# mimamori-hat-v03.net
KiCad netlist of a schematic drawn in EAGLE
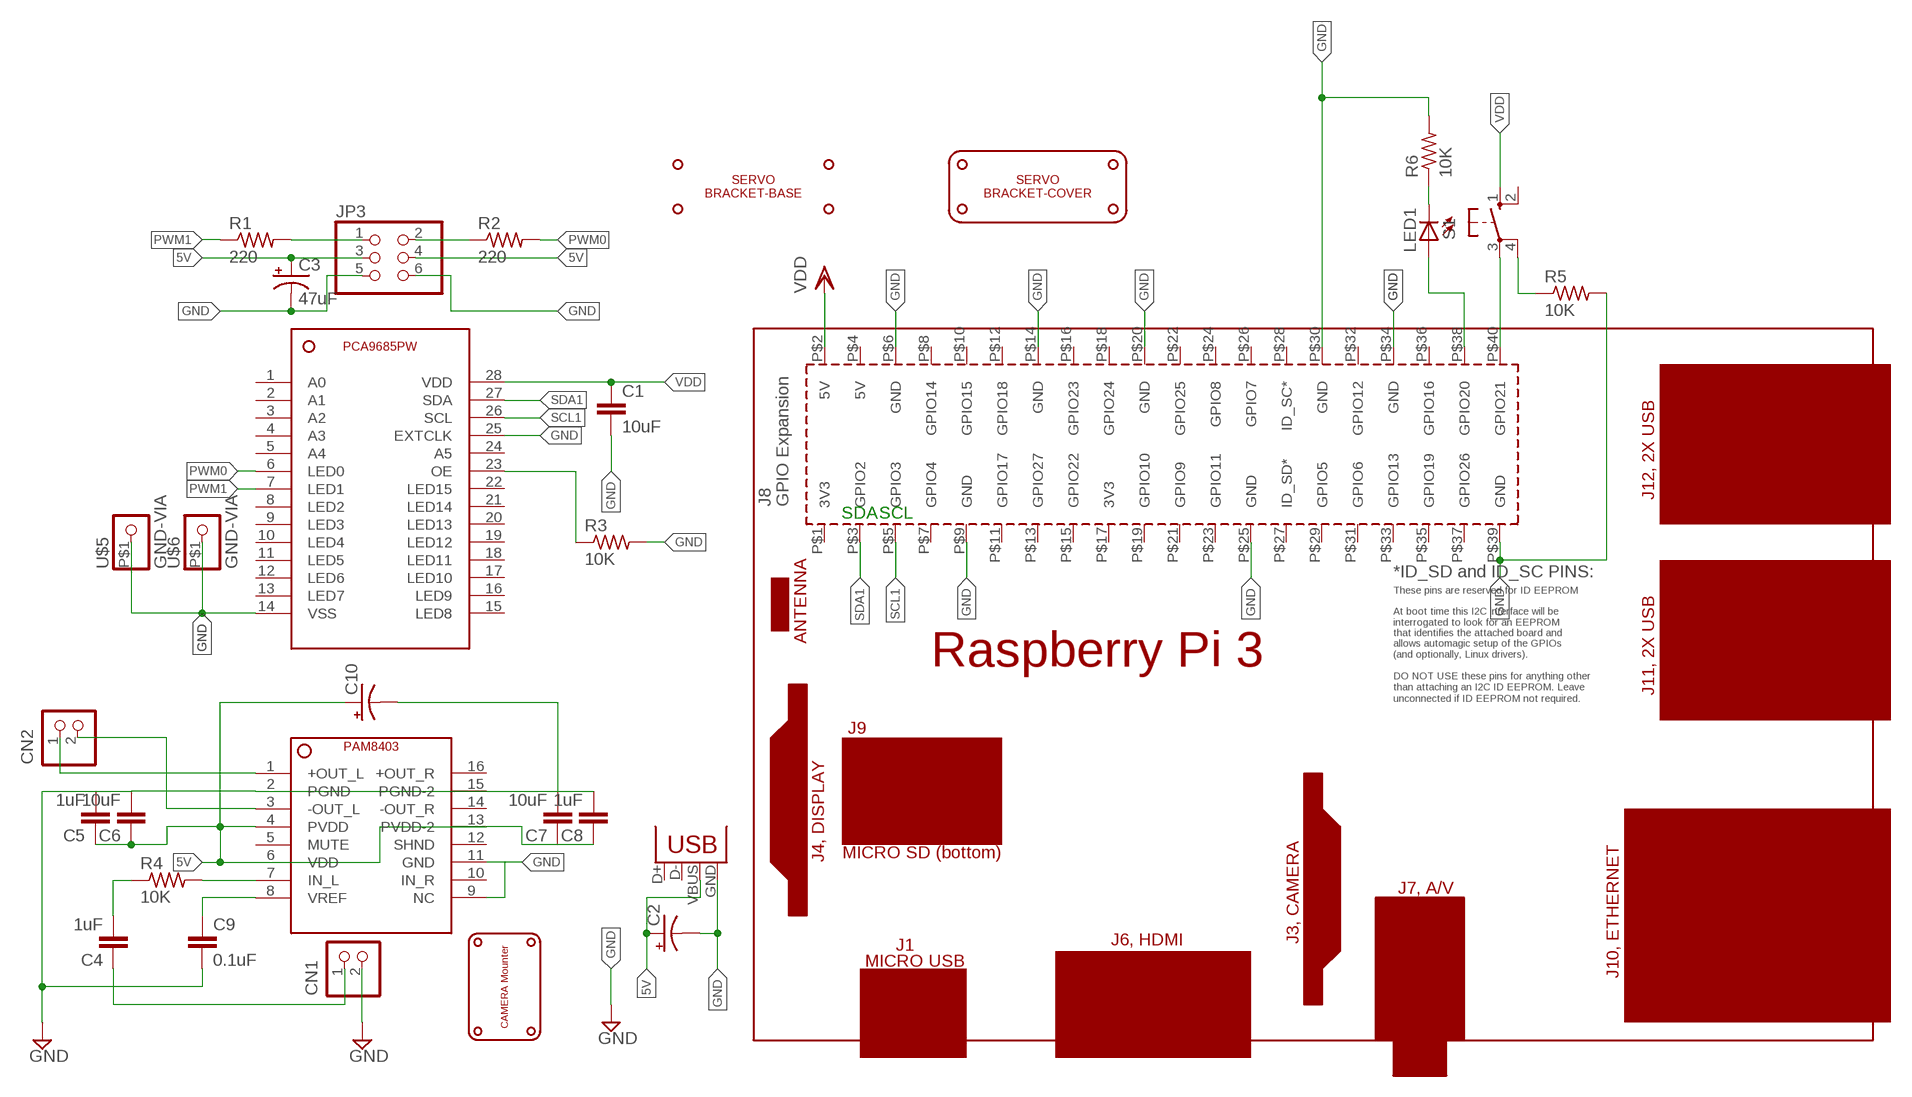
[diagram p0: schematic, sheet 1]

(export (version "E")
  (design (tool "Eeschema 10.0.6"))
  (components
    (comp (ref "C1")
      (value "10uF")
      (footprint "eagle-import:C0805")
      (libsource (lib "eagle-import") (part "C-EUC0805"))
    )
    (comp (ref "C2")
      (value "CPOL-US153CLV-0810")
      (footprint "eagle-import:153CLV-0810")
      (libsource (lib "eagle-import") (part "CPOL-US153CLV-0810"))
    )
    (comp (ref "C3")
      (value "47uF")
      (footprint "eagle-import:153CLV-0605")
      (libsource (lib "eagle-import") (part "CPOL-US153CLV-0605"))
    )
    (comp (ref "C4")
      (value "1uF")
      (footprint "eagle-import:C0805")
      (libsource (lib "eagle-import") (part "C-EUC0805"))
    )
    (comp (ref "C5")
      (value "1uF")
      (footprint "eagle-import:C0805")
      (libsource (lib "eagle-import") (part "C-EUC0805"))
    )
    (comp (ref "C6")
      (value "10uF")
      (footprint "eagle-import:C0805")
      (libsource (lib "eagle-import") (part "C-EUC0805"))
    )
    (comp (ref "C7")
      (value "10uF")
      (footprint "eagle-import:C0805")
      (libsource (lib "eagle-import") (part "C-EUC0805"))
    )
    (comp (ref "C8")
      (value "1uF")
      (footprint "eagle-import:C0805")
      (libsource (lib "eagle-import") (part "C-EUC0805"))
    )
    (comp (ref "C9")
      (value "0.1uF")
      (footprint "eagle-import:C0805")
      (libsource (lib "eagle-import") (part "C-EUC0805"))
    )
    (comp (ref "C10")
      (value "CPOL-US153CLV-0810")
      (footprint "eagle-import:153CLV-0810")
      (libsource (lib "eagle-import") (part "CPOL-US153CLV-0810"))
    )
    (comp (ref "CN1")
      (value "B2B-PH-K-S")
      (footprint "eagle-import:B2B-PH-K-S")
      (libsource (lib "eagle-import") (part "B2B-PH-K-S"))
    )
    (comp (ref "CN2")
      (value "B2B-PH-K-S")
      (footprint "eagle-import:B2B-PH-K-S")
      (libsource (lib "eagle-import") (part "B2B-PH-K-S"))
    )
    (comp (ref "JP1")
      (value "USB-MICROB")
      (footprint "eagle-import:USB-MICROB")
      (libsource (lib "eagle-import") (part "USB-MICROB"))
    )
    (comp (ref "JP3")
      (value "PINHD-2X3")
      (footprint "eagle-import:2X03")
      (libsource (lib "eagle-import") (part "PINHD-2X3"))
    )
    (comp (ref "LED1")
      (value "LED3MM")
      (footprint "eagle-import:LED3MM")
      (libsource (lib "eagle-import") (part "LED3MM"))
    )
    (comp (ref "PCB1")
      (value "RPI3")
      (footprint "eagle-import:RPI3")
      (libsource (lib "eagle-import") (part "RPI3"))
    )
    (comp (ref "R1")
      (value "220")
      (footprint "eagle-import:R0805")
      (libsource (lib "eagle-import") (part "R-US_R0805"))
    )
    (comp (ref "R2")
      (value "220")
      (footprint "eagle-import:R0805")
      (libsource (lib "eagle-import") (part "R-US_R0805"))
    )
    (comp (ref "R3")
      (value "10K")
      (footprint "eagle-import:R0805")
      (libsource (lib "eagle-import") (part "R-US_R0805"))
    )
    (comp (ref "R4")
      (value "10K")
      (footprint "eagle-import:R0805")
      (libsource (lib "eagle-import") (part "R-US_R0805"))
    )
    (comp (ref "R5")
      (value "10K")
      (footprint "eagle-import:R0805")
      (libsource (lib "eagle-import") (part "R-US_R0805"))
    )
    (comp (ref "R6")
      (value "10K")
      (footprint "eagle-import:R0805")
      (libsource (lib "eagle-import") (part "R-US_R0805"))
    )
    (comp (ref "S1")
      (value "10-XX")
      (footprint "eagle-import:B3F-10XX")
      (fields (field (name "MPN") "B3F-1000"))
      (libsource (lib "eagle-import") (part "10-XX"))
    )
    (comp (ref "U$1")
      (value "PAM8403")
      (footprint "eagle-import:SOP16")
      (libsource (lib "eagle-import") (part "PAM8403"))
    )
    (comp (ref "U$2")
      (value "PCA9685PW")
      (footprint "eagle-import:TSSOP28")
      (libsource (lib "eagle-import") (part "PCA9685PW"))
    )
    (comp (ref "U$3")
      (value "CAMERA-MOUNTER")
      (footprint "eagle-import:CAMERA-MOUNTER")
      (libsource (lib "eagle-import") (part "CAMERA-MOUNTER"))
    )
    (comp (ref "U$4")
      (value "SERVO-BRACKET-BASE")
      (footprint "eagle-import:SERVO-BRACKET")
      (libsource (lib "eagle-import") (part "SERVO-BRACKET-BASE"))
    )
    (comp (ref "U$5")
      (value "GND-VIA")
      (footprint "eagle-import:GND-VIA")
      (libsource (lib "eagle-import") (part "GND-VIA"))
    )
    (comp (ref "U$6")
      (value "GND-VIA")
      (footprint "eagle-import:GND-VIA")
      (libsource (lib "eagle-import") (part "GND-VIA"))
    )
    (comp (ref "U$7")
      (value "SERVO-BRACKER-COVER")
      (footprint "eagle-import:SERVO-BRACKET-COVER")
      (libsource (lib "eagle-import") (part "SERVO-BRACKER-COVER"))
    )
  )
  (nets
    (net (code "1") (name "5V") (class "Default")
      (node (ref "C10") (pin "+") (pinfunction "+_+") (pintype "passive"))
      (node (ref "C2") (pin "+") (pinfunction "+_+") (pintype "passive"))
      (node (ref "C3") (pin "+") (pinfunction "+_+") (pintype "passive"))
      (node (ref "C5") (pin "1") (pinfunction "1_1") (pintype "passive"))
      (node (ref "C6") (pin "1") (pinfunction "1_1") (pintype "passive"))
      (node (ref "C7") (pin "1") (pinfunction "1_1") (pintype "passive"))
      (node (ref "C8") (pin "1") (pinfunction "1_1") (pintype "passive"))
      (node (ref "JP1") (pin "VBUS") (pinfunction "VBUS_VBUS") (pintype "bidirectional"))
      (node (ref "JP3") (pin "3") (pinfunction "3_3") (pintype "passive"))
      (node (ref "JP3") (pin "4") (pinfunction "4_4") (pintype "passive"))
      (node (ref "U$1") (pin "13") (pinfunction "PVDD-2_13") (pintype "bidirectional"))
      (node (ref "U$1") (pin "4") (pinfunction "PVDD_4") (pintype "bidirectional"))
      (node (ref "U$1") (pin "6") (pinfunction "VDD_6") (pintype "bidirectional"))
    )
    (net (code "2") (name "GND") (class "Default")
      (node (ref "C1") (pin "2") (pinfunction "2_2") (pintype "passive"))
      (node (ref "C10") (pin "-") (pinfunction "-_-") (pintype "passive"))
      (node (ref "C2") (pin "-") (pinfunction "-_-") (pintype "passive"))
      (node (ref "C3") (pin "-") (pinfunction "-_-") (pintype "passive"))
      (node (ref "C5") (pin "2") (pinfunction "2_2") (pintype "passive"))
      (node (ref "C6") (pin "2") (pinfunction "2_2") (pintype "passive"))
      (node (ref "C7") (pin "2") (pinfunction "2_2") (pintype "passive"))
      (node (ref "C8") (pin "2") (pinfunction "2_2") (pintype "passive"))
      (node (ref "C9") (pin "2") (pinfunction "2_2") (pintype "passive"))
      (node (ref "CN1") (pin "2") (pinfunction "2_2") (pintype "passive"))
      (node (ref "JP1") (pin "GND") (pinfunction "GND_GND") (pintype "bidirectional"))
      (node (ref "JP3") (pin "5") (pinfunction "5_5") (pintype "passive"))
      (node (ref "JP3") (pin "6") (pinfunction "6_6") (pintype "passive"))
      (node (ref "PCB1") (pin "P$14") (pinfunction "GND_P$14") (pintype "bidirectional"))
      (node (ref "PCB1") (pin "P$20") (pinfunction "GND_P$20") (pintype "bidirectional"))
      (node (ref "PCB1") (pin "P$25") (pinfunction "GND_P$25") (pintype "bidirectional"))
      (node (ref "PCB1") (pin "P$30") (pinfunction "GND_P$30") (pintype "bidirectional"))
      (node (ref "PCB1") (pin "P$34") (pinfunction "GND_P$34") (pintype "bidirectional"))
      (node (ref "PCB1") (pin "P$39") (pinfunction "GND_P$39") (pintype "bidirectional"))
      (node (ref "PCB1") (pin "P$6") (pinfunction "GND_P$6") (pintype "bidirectional"))
      (node (ref "PCB1") (pin "P$9") (pinfunction "GND_P$9") (pintype "bidirectional"))
      (node (ref "R3") (pin "2") (pinfunction "2_2") (pintype "passive"))
      (node (ref "R5") (pin "2") (pinfunction "2_2") (pintype "passive"))
      (node (ref "R6") (pin "2") (pinfunction "2_2") (pintype "passive"))
      (node (ref "U$1") (pin "11") (pinfunction "GND_11") (pintype "bidirectional"))
      (node (ref "U$1") (pin "15") (pinfunction "PGND-2_15") (pintype "bidirectional"))
      (node (ref "U$1") (pin "2") (pinfunction "PGND_2") (pintype "bidirectional"))
      (node (ref "U$1") (pin "9") (pinfunction "NC_9") (pintype "bidirectional"))
      (node (ref "U$2") (pin "14") (pinfunction "VSS_14") (pintype "bidirectional"))
      (node (ref "U$2") (pin "25") (pinfunction "EXTCLK_25") (pintype "bidirectional"))
      (node (ref "U$5") (pin "P$1") (pinfunction "1_P$1") (pintype "passive"))
      (node (ref "U$6") (pin "P$1") (pinfunction "1_P$1") (pintype "passive"))
    )
    (net (code "3") (name "Net-(C4-Pad1)") (class "Default")
      (node (ref "C4") (pin "1") (pinfunction "1_1") (pintype "passive"))
      (node (ref "CN1") (pin "1") (pinfunction "1_1") (pintype "passive"))
    )
    (net (code "4") (name "Net-(C4-Pad2)") (class "Default")
      (node (ref "C4") (pin "2") (pinfunction "2_2") (pintype "passive"))
      (node (ref "R4") (pin "1") (pinfunction "1_1") (pintype "passive"))
    )
    (net (code "5") (name "Net-(JP3-Pad1)") (class "Default")
      (node (ref "JP3") (pin "1") (pinfunction "1_1") (pintype "passive"))
      (node (ref "R1") (pin "2") (pinfunction "2_2") (pintype "passive"))
    )
    (net (code "6") (name "Net-(JP3-Pad2)") (class "Default")
      (node (ref "JP3") (pin "2") (pinfunction "2_2") (pintype "passive"))
      (node (ref "R2") (pin "1") (pinfunction "1_1") (pintype "passive"))
    )
    (net (code "7") (name "Net-(LED1-C)") (class "Default")
      (node (ref "LED1") (pin "K") (pinfunction "C_K") (pintype "passive"))
      (node (ref "R6") (pin "1") (pinfunction "1_1") (pintype "passive"))
    )
    (net (code "8") (name "Net-(PCB1-GPIO20)") (class "Default")
      (node (ref "LED1") (pin "A") (pinfunction "A_A") (pintype "passive"))
      (node (ref "PCB1") (pin "P$38") (pinfunction "GPIO20_P$38") (pintype "bidirectional"))
    )
    (net (code "9") (name "Net-(PCB1-GPIO21)") (class "Default")
      (node (ref "PCB1") (pin "P$40") (pinfunction "GPIO21_P$40") (pintype "bidirectional"))
      (node (ref "S1") (pin "3") (pinfunction "P_3") (pintype "passive"))
    )
    (net (code "10") (name "Net-(S1-P1)") (class "Default")
      (node (ref "R5") (pin "1") (pinfunction "1_1") (pintype "passive"))
      (node (ref "S1") (pin "4") (pinfunction "P1_4") (pintype "passive"))
    )
    (net (code "11") (name "Net-(U$1-+OUT_L)") (class "Default")
      (node (ref "CN2") (pin "1") (pinfunction "1_1") (pintype "passive"))
      (node (ref "U$1") (pin "1") (pinfunction "+OUT_L_1") (pintype "bidirectional"))
    )
    (net (code "12") (name "Net-(U$1--OUT_L)") (class "Default")
      (node (ref "CN2") (pin "2") (pinfunction "2_2") (pintype "passive"))
      (node (ref "U$1") (pin "3") (pinfunction "-OUT_L_3") (pintype "bidirectional"))
    )
    (net (code "13") (name "Net-(U$1-IN_L)") (class "Default")
      (node (ref "R4") (pin "2") (pinfunction "2_2") (pintype "passive"))
      (node (ref "U$1") (pin "7") (pinfunction "IN_L_7") (pintype "bidirectional"))
    )
    (net (code "14") (name "Net-(U$1-VREF)") (class "Default")
      (node (ref "C9") (pin "1") (pinfunction "1_1") (pintype "passive"))
      (node (ref "U$1") (pin "8") (pinfunction "VREF_8") (pintype "bidirectional"))
    )
    (net (code "15") (name "Net-(U$2-OE)") (class "Default")
      (node (ref "R3") (pin "1") (pinfunction "1_1") (pintype "passive"))
      (node (ref "U$2") (pin "23") (pinfunction "OE_23") (pintype "bidirectional"))
    )
    (net (code "16") (name "PWM0") (class "Default")
      (node (ref "R2") (pin "2") (pinfunction "2_2") (pintype "passive"))
      (node (ref "U$2") (pin "6") (pinfunction "LED0_6") (pintype "bidirectional"))
    )
    (net (code "17") (name "PWM1") (class "Default")
      (node (ref "R1") (pin "1") (pinfunction "1_1") (pintype "passive"))
      (node (ref "U$2") (pin "7") (pinfunction "LED1_7") (pintype "bidirectional"))
    )
    (net (code "18") (name "SCL1") (class "Default")
      (node (ref "PCB1") (pin "P$5") (pinfunction "GPIO3_P$5") (pintype "bidirectional"))
      (node (ref "U$2") (pin "26") (pinfunction "SCL_26") (pintype "bidirectional"))
    )
    (net (code "19") (name "SDA1") (class "Default")
      (node (ref "PCB1") (pin "P$3") (pinfunction "GPIO2_P$3") (pintype "bidirectional"))
      (node (ref "U$2") (pin "27") (pinfunction "SDA_27") (pintype "bidirectional"))
    )
    (net (code "20") (name "VDD") (class "Default")
      (node (ref "C1") (pin "1") (pinfunction "1_1") (pintype "passive"))
      (node (ref "PCB1") (pin "P$2") (pinfunction "5V_P$2") (pintype "bidirectional"))
      (node (ref "S1") (pin "1") (pinfunction "S_1") (pintype "passive"))
      (node (ref "U$2") (pin "28") (pinfunction "VDD_28") (pintype "bidirectional"))
    )
    (net (code "21") (name "unconnected-(JP1-PadD+)") (class "Default")
      (node (ref "JP1") (pin "D+") (pinfunction "D+_D+") (pintype "bidirectional"))
    )
    (net (code "22") (name "unconnected-(JP1-PadD-)") (class "Default")
      (node (ref "JP1") (pin "D-") (pinfunction "D-_D-") (pintype "bidirectional"))
    )
    (net (code "23") (name "unconnected-(PCB1-3V3-PadP$1)") (class "Default")
      (node (ref "PCB1") (pin "P$1") (pinfunction "3V3_P$1") (pintype "bidirectional"))
    )
    (net (code "24") (name "unconnected-(PCB1-3V3-PadP$17)") (class "Default")
      (node (ref "PCB1") (pin "P$17") (pinfunction "3V3_P$17") (pintype "bidirectional"))
    )
    (net (code "25") (name "unconnected-(PCB1-5V-PadP$4)") (class "Default")
      (node (ref "PCB1") (pin "P$4") (pinfunction "5V_P$4") (pintype "bidirectional"))
    )
    (net (code "26") (name "unconnected-(PCB1-GPIO4-PadP$7)") (class "Default")
      (node (ref "PCB1") (pin "P$7") (pinfunction "GPIO4_P$7") (pintype "bidirectional"))
    )
    (net (code "27") (name "unconnected-(PCB1-GPIO5-PadP$29)") (class "Default")
      (node (ref "PCB1") (pin "P$29") (pinfunction "GPIO5_P$29") (pintype "bidirectional"))
    )
    (net (code "28") (name "unconnected-(PCB1-GPIO6-PadP$31)") (class "Default")
      (node (ref "PCB1") (pin "P$31") (pinfunction "GPIO6_P$31") (pintype "bidirectional"))
    )
    (net (code "29") (name "unconnected-(PCB1-GPIO7-PadP$26)") (class "Default")
      (node (ref "PCB1") (pin "P$26") (pinfunction "GPIO7_P$26") (pintype "bidirectional"))
    )
    (net (code "30") (name "unconnected-(PCB1-GPIO8-PadP$24)") (class "Default")
      (node (ref "PCB1") (pin "P$24") (pinfunction "GPIO8_P$24") (pintype "bidirectional"))
    )
    (net (code "31") (name "unconnected-(PCB1-GPIO9-PadP$21)") (class "Default")
      (node (ref "PCB1") (pin "P$21") (pinfunction "GPIO9_P$21") (pintype "bidirectional"))
    )
    (net (code "32") (name "unconnected-(PCB1-GPIO10-PadP$19)") (class "Default")
      (node (ref "PCB1") (pin "P$19") (pinfunction "GPIO10_P$19") (pintype "bidirectional"))
    )
    (net (code "33") (name "unconnected-(PCB1-GPIO11-PadP$23)") (class "Default")
      (node (ref "PCB1") (pin "P$23") (pinfunction "GPIO11_P$23") (pintype "bidirectional"))
    )
    (net (code "34") (name "unconnected-(PCB1-GPIO12-PadP$32)") (class "Default")
      (node (ref "PCB1") (pin "P$32") (pinfunction "GPIO12_P$32") (pintype "bidirectional"))
    )
    (net (code "35") (name "unconnected-(PCB1-GPIO13-PadP$33)") (class "Default")
      (node (ref "PCB1") (pin "P$33") (pinfunction "GPIO13_P$33") (pintype "bidirectional"))
    )
    (net (code "36") (name "unconnected-(PCB1-GPIO14-PadP$8)") (class "Default")
      (node (ref "PCB1") (pin "P$8") (pinfunction "GPIO14_P$8") (pintype "bidirectional"))
    )
    (net (code "37") (name "unconnected-(PCB1-GPIO15-PadP$10)") (class "Default")
      (node (ref "PCB1") (pin "P$10") (pinfunction "GPIO15_P$10") (pintype "bidirectional"))
    )
    (net (code "38") (name "unconnected-(PCB1-GPIO16-PadP$36)") (class "Default")
      (node (ref "PCB1") (pin "P$36") (pinfunction "GPIO16_P$36") (pintype "bidirectional"))
    )
    (net (code "39") (name "unconnected-(PCB1-GPIO17-PadP$11)") (class "Default")
      (node (ref "PCB1") (pin "P$11") (pinfunction "GPIO17_P$11") (pintype "bidirectional"))
    )
    (net (code "40") (name "unconnected-(PCB1-GPIO18-PadP$12)") (class "Default")
      (node (ref "PCB1") (pin "P$12") (pinfunction "GPIO18_P$12") (pintype "bidirectional"))
    )
    (net (code "41") (name "unconnected-(PCB1-GPIO19-PadP$35)") (class "Default")
      (node (ref "PCB1") (pin "P$35") (pinfunction "GPIO19_P$35") (pintype "bidirectional"))
    )
    (net (code "42") (name "unconnected-(PCB1-GPIO22-PadP$15)") (class "Default")
      (node (ref "PCB1") (pin "P$15") (pinfunction "GPIO22_P$15") (pintype "bidirectional"))
    )
    (net (code "43") (name "unconnected-(PCB1-GPIO23-PadP$16)") (class "Default")
      (node (ref "PCB1") (pin "P$16") (pinfunction "GPIO23_P$16") (pintype "bidirectional"))
    )
    (net (code "44") (name "unconnected-(PCB1-GPIO24-PadP$18)") (class "Default")
      (node (ref "PCB1") (pin "P$18") (pinfunction "GPIO24_P$18") (pintype "bidirectional"))
    )
    (net (code "45") (name "unconnected-(PCB1-GPIO25-PadP$22)") (class "Default")
      (node (ref "PCB1") (pin "P$22") (pinfunction "GPIO25_P$22") (pintype "bidirectional"))
    )
    (net (code "46") (name "unconnected-(PCB1-GPIO26-PadP$37)") (class "Default")
      (node (ref "PCB1") (pin "P$37") (pinfunction "GPIO26_P$37") (pintype "bidirectional"))
    )
    (net (code "47") (name "unconnected-(PCB1-GPIO27-PadP$13)") (class "Default")
      (node (ref "PCB1") (pin "P$13") (pinfunction "GPIO27_P$13") (pintype "bidirectional"))
    )
    (net (code "48") (name "unconnected-(PCB1-ID_SC*-PadP$28)") (class "Default")
      (node (ref "PCB1") (pin "P$28") (pinfunction "ID_SC*_P$28") (pintype "bidirectional"))
    )
    (net (code "49") (name "unconnected-(PCB1-ID_SD*-PadP$27)") (class "Default")
      (node (ref "PCB1") (pin "P$27") (pinfunction "ID_SD*_P$27") (pintype "bidirectional"))
    )
    (net (code "50") (name "unconnected-(S1-S1-Pad2)") (class "Default")
      (node (ref "S1") (pin "2") (pinfunction "S1_2") (pintype "passive"))
    )
    (net (code "51") (name "unconnected-(U$1-+OUT_R-Pad16)") (class "Default")
      (node (ref "U$1") (pin "16") (pinfunction "+OUT_R_16") (pintype "bidirectional"))
    )
    (net (code "52") (name "unconnected-(U$1--OUT_R-Pad14)") (class "Default")
      (node (ref "U$1") (pin "14") (pinfunction "-OUT_R_14") (pintype "bidirectional"))
    )
    (net (code "53") (name "unconnected-(U$1-IN_R-Pad10)") (class "Default")
      (node (ref "U$1") (pin "10") (pinfunction "IN_R_10") (pintype "bidirectional"))
    )
    (net (code "54") (name "unconnected-(U$1-MUTE-Pad5)") (class "Default")
      (node (ref "U$1") (pin "5") (pinfunction "MUTE_5") (pintype "bidirectional"))
    )
    (net (code "55") (name "unconnected-(U$1-SHND-Pad12)") (class "Default")
      (node (ref "U$1") (pin "12") (pinfunction "SHND_12") (pintype "bidirectional"))
    )
    (net (code "56") (name "unconnected-(U$2-A0-Pad1)") (class "Default")
      (node (ref "U$2") (pin "1") (pinfunction "A0_1") (pintype "bidirectional"))
    )
    (net (code "57") (name "unconnected-(U$2-A1-Pad2)") (class "Default")
      (node (ref "U$2") (pin "2") (pinfunction "A1_2") (pintype "bidirectional"))
    )
    (net (code "58") (name "unconnected-(U$2-A2-Pad3)") (class "Default")
      (node (ref "U$2") (pin "3") (pinfunction "A2_3") (pintype "bidirectional"))
    )
    (net (code "59") (name "unconnected-(U$2-A3-Pad4)") (class "Default")
      (node (ref "U$2") (pin "4") (pinfunction "A3_4") (pintype "bidirectional"))
    )
    (net (code "60") (name "unconnected-(U$2-A4-Pad5)") (class "Default")
      (node (ref "U$2") (pin "5") (pinfunction "A4_5") (pintype "bidirectional"))
    )
    (net (code "61") (name "unconnected-(U$2-A5-Pad24)") (class "Default")
      (node (ref "U$2") (pin "24") (pinfunction "A5_24") (pintype "bidirectional"))
    )
    (net (code "62") (name "unconnected-(U$2-LED2-Pad8)") (class "Default")
      (node (ref "U$2") (pin "8") (pinfunction "LED2_8") (pintype "bidirectional"))
    )
    (net (code "63") (name "unconnected-(U$2-LED3-Pad9)") (class "Default")
      (node (ref "U$2") (pin "9") (pinfunction "LED3_9") (pintype "bidirectional"))
    )
    (net (code "64") (name "unconnected-(U$2-LED4-Pad10)") (class "Default")
      (node (ref "U$2") (pin "10") (pinfunction "LED4_10") (pintype "bidirectional"))
    )
    (net (code "65") (name "unconnected-(U$2-LED5-Pad11)") (class "Default")
      (node (ref "U$2") (pin "11") (pinfunction "LED5_11") (pintype "bidirectional"))
    )
    (net (code "66") (name "unconnected-(U$2-LED6-Pad12)") (class "Default")
      (node (ref "U$2") (pin "12") (pinfunction "LED6_12") (pintype "bidirectional"))
    )
    (net (code "67") (name "unconnected-(U$2-LED7-Pad13)") (class "Default")
      (node (ref "U$2") (pin "13") (pinfunction "LED7_13") (pintype "bidirectional"))
    )
    (net (code "68") (name "unconnected-(U$2-LED8-Pad15)") (class "Default")
      (node (ref "U$2") (pin "15") (pinfunction "LED8_15") (pintype "bidirectional"))
    )
    (net (code "69") (name "unconnected-(U$2-LED9-Pad16)") (class "Default")
      (node (ref "U$2") (pin "16") (pinfunction "LED9_16") (pintype "bidirectional"))
    )
    (net (code "70") (name "unconnected-(U$2-LED10-Pad17)") (class "Default")
      (node (ref "U$2") (pin "17") (pinfunction "LED10_17") (pintype "bidirectional"))
    )
    (net (code "71") (name "unconnected-(U$2-LED11-Pad18)") (class "Default")
      (node (ref "U$2") (pin "18") (pinfunction "LED11_18") (pintype "bidirectional"))
    )
    (net (code "72") (name "unconnected-(U$2-LED12-Pad19)") (class "Default")
      (node (ref "U$2") (pin "19") (pinfunction "LED12_19") (pintype "bidirectional"))
    )
    (net (code "73") (name "unconnected-(U$2-LED13-Pad20)") (class "Default")
      (node (ref "U$2") (pin "20") (pinfunction "LED13_20") (pintype "bidirectional"))
    )
    (net (code "74") (name "unconnected-(U$2-LED14-Pad21)") (class "Default")
      (node (ref "U$2") (pin "21") (pinfunction "LED14_21") (pintype "bidirectional"))
    )
    (net (code "75") (name "unconnected-(U$2-LED15-Pad22)") (class "Default")
      (node (ref "U$2") (pin "22") (pinfunction "LED15_22") (pintype "bidirectional"))
    )
  )
)
